# Aerothrust_Module_Stm32_PCB.net
KiCad netlist of a schematic drawn in EAGLE
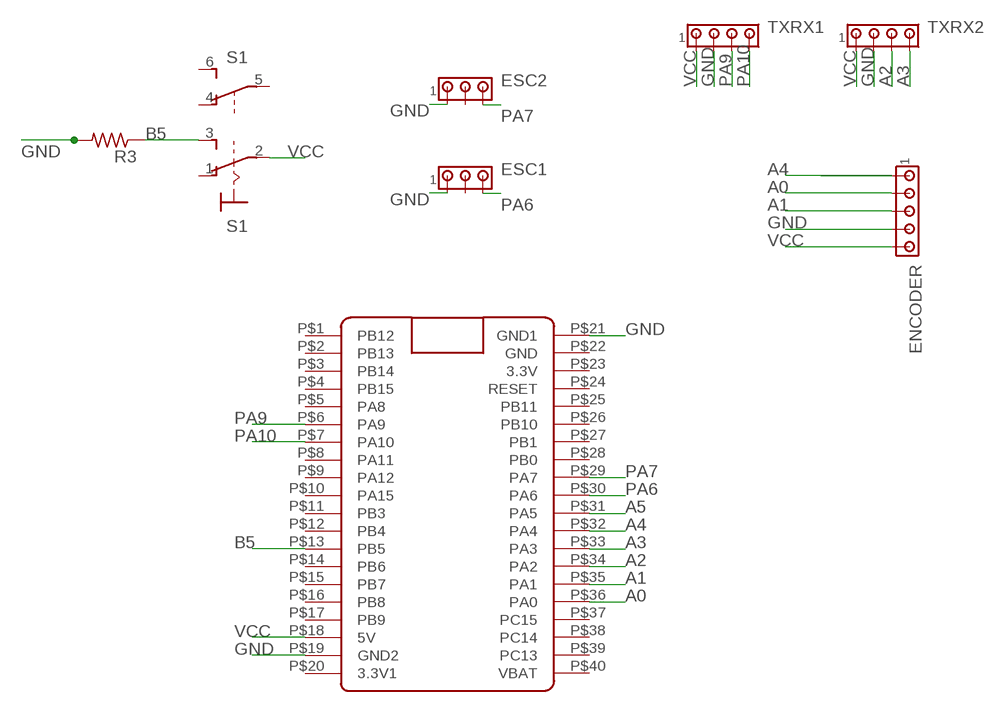
[diagram p0: schematic, sheet 1]

(export (version "E")
  (design (tool "Eeschema 10.0.6"))
  (components
    (comp (ref "ENCODER")
      (value "MTA05-100")
      (footprint "eagle-import:10X05MTA")
      (libsource (lib "eagle-import") (part "MTA05-100"))
    )
    (comp (ref "ESC1")
      (value "MTA03-100")
      (footprint "eagle-import:10X03MTA")
      (libsource (lib "eagle-import") (part "MTA03-100"))
    )
    (comp (ref "ESC2")
      (value "MTA03-100")
      (footprint "eagle-import:10X03MTA")
      (libsource (lib "eagle-import") (part "MTA03-100"))
    )
    (comp (ref "R3")
      (value "R-US_0207/10")
      (footprint "eagle-import:0207_10")
      (libsource (lib "eagle-import") (part "R-US_0207/10"))
    )
    (comp (ref "S1")
      (value "320-938")
      (footprint "eagle-import:320-938")
      (libsource (lib "eagle-import") (part "320-938"))
    )
    (comp (ref "TXRX1")
      (value "MTA04-100")
      (footprint "eagle-import:10X04MTA")
      (libsource (lib "eagle-import") (part "MTA04-100"))
    )
    (comp (ref "TXRX2")
      (value "MTA04-100")
      (footprint "eagle-import:10X04MTA")
      (libsource (lib "eagle-import") (part "MTA04-100"))
    )
    (comp (ref "U$1")
      (value "BLUE_PILL")
      (footprint "eagle-import:BLUE_PILL")
      (libsource (lib "eagle-import") (part "BLUE_PILL"))
    )
  )
  (nets
    (net (code "1") (name "/A0") (class "Default")
      (node (ref "ENCODER") (pin "2") (pinfunction "2_2") (pintype "passive"))
      (node (ref "U$1") (pin "P$36") (pinfunction "PA0_P$36") (pintype "bidirectional"))
    )
    (net (code "2") (name "/A1") (class "Default")
      (node (ref "ENCODER") (pin "3") (pinfunction "3_3") (pintype "passive"))
      (node (ref "U$1") (pin "P$35") (pinfunction "PA1_P$35") (pintype "bidirectional"))
    )
    (net (code "3") (name "/A2") (class "Default")
      (node (ref "TXRX2") (pin "3") (pinfunction "3_3") (pintype "passive"))
      (node (ref "U$1") (pin "P$34") (pinfunction "PA2_P$34") (pintype "bidirectional"))
    )
    (net (code "4") (name "/A3") (class "Default")
      (node (ref "TXRX2") (pin "4") (pinfunction "4_4") (pintype "passive"))
      (node (ref "U$1") (pin "P$33") (pinfunction "PA3_P$33") (pintype "bidirectional"))
    )
    (net (code "5") (name "/A4") (class "Default")
      (node (ref "ENCODER") (pin "1") (pinfunction "1_1") (pintype "passive"))
      (node (ref "U$1") (pin "P$32") (pinfunction "PA4_P$32") (pintype "bidirectional"))
    )
    (net (code "6") (name "/A5") (class "Default")
      (node (ref "U$1") (pin "P$31") (pinfunction "PA5_P$31") (pintype "bidirectional"))
    )
    (net (code "7") (name "/B5") (class "Default")
      (node (ref "R3") (pin "1") (pinfunction "1_1") (pintype "passive"))
      (node (ref "S1") (pin "3") (pinfunction "S_3") (pintype "passive"))
      (node (ref "U$1") (pin "P$13") (pinfunction "PB5_P$13") (pintype "bidirectional"))
    )
    (net (code "8") (name "/GND") (class "Default")
      (node (ref "ENCODER") (pin "4") (pinfunction "4_4") (pintype "passive"))
      (node (ref "ESC1") (pin "1") (pinfunction "1_1") (pintype "passive"))
      (node (ref "ESC2") (pin "1") (pinfunction "1_1") (pintype "passive"))
      (node (ref "R3") (pin "2") (pinfunction "2_2") (pintype "passive"))
      (node (ref "TXRX1") (pin "2") (pinfunction "2_2") (pintype "passive"))
      (node (ref "TXRX2") (pin "2") (pinfunction "2_2") (pintype "passive"))
      (node (ref "U$1") (pin "P$19") (pinfunction "GND2_P$19") (pintype "bidirectional"))
      (node (ref "U$1") (pin "P$21") (pinfunction "GND1_P$21") (pintype "power_in"))
    )
    (net (code "9") (name "/PA6") (class "Default")
      (node (ref "ESC1") (pin "3") (pinfunction "3_3") (pintype "passive"))
      (node (ref "U$1") (pin "P$30") (pinfunction "PA6_P$30") (pintype "bidirectional"))
    )
    (net (code "10") (name "/PA7") (class "Default")
      (node (ref "ESC2") (pin "3") (pinfunction "3_3") (pintype "passive"))
      (node (ref "U$1") (pin "P$29") (pinfunction "PA7_P$29") (pintype "bidirectional"))
    )
    (net (code "11") (name "/PA9") (class "Default")
      (node (ref "TXRX1") (pin "3") (pinfunction "3_3") (pintype "passive"))
      (node (ref "U$1") (pin "P$6") (pinfunction "PA9_P$6") (pintype "bidirectional"))
    )
    (net (code "12") (name "/PA10") (class "Default")
      (node (ref "TXRX1") (pin "4") (pinfunction "4_4") (pintype "passive"))
      (node (ref "U$1") (pin "P$7") (pinfunction "PA10_P$7") (pintype "bidirectional"))
    )
    (net (code "13") (name "/VCC") (class "Default")
      (node (ref "ENCODER") (pin "5") (pinfunction "5_5") (pintype "passive"))
      (node (ref "S1") (pin "2") (pinfunction "P_2") (pintype "passive"))
      (node (ref "TXRX1") (pin "1") (pinfunction "1_1") (pintype "passive"))
      (node (ref "TXRX2") (pin "1") (pinfunction "1_1") (pintype "passive"))
      (node (ref "U$1") (pin "P$18") (pinfunction "5V_P$18") (pintype "bidirectional"))
    )
    (net (code "14") (name "unconnected-(ESC1-Pad2)") (class "Default")
      (node (ref "ESC1") (pin "2") (pinfunction "2_2") (pintype "passive"))
    )
    (net (code "15") (name "unconnected-(ESC2-Pad2)") (class "Default")
      (node (ref "ESC2") (pin "2") (pinfunction "2_2") (pintype "passive"))
    )
    (net (code "16") (name "unconnected-(S1A-O-Pad1)") (class "Default")
      (node (ref "S1") (pin "1") (pinfunction "O_1") (pintype "passive"))
    )
    (net (code "17") (name "unconnected-(S1B-O-Pad4)") (class "Default")
      (node (ref "S1") (pin "4") (pinfunction "O_4") (pintype "passive"))
    )
    (net (code "18") (name "unconnected-(S1B-P-Pad5)") (class "Default")
      (node (ref "S1") (pin "5") (pinfunction "P_5") (pintype "passive"))
    )
    (net (code "19") (name "unconnected-(S1B-S-Pad6)") (class "Default")
      (node (ref "S1") (pin "6") (pinfunction "S_6") (pintype "passive"))
    )
    (net (code "20") (name "unconnected-(U$1-3.3V-PadP$23)") (class "Default")
      (node (ref "U$1") (pin "P$23") (pinfunction "3.3V_P$23") (pintype "bidirectional"))
    )
    (net (code "21") (name "unconnected-(U$1-3.3V1-PadP$20)") (class "Default")
      (node (ref "U$1") (pin "P$20") (pinfunction "3.3V1_P$20") (pintype "bidirectional"))
    )
    (net (code "22") (name "unconnected-(U$1-GND-PadP$22)") (class "Default")
      (node (ref "U$1") (pin "P$22") (pinfunction "GND_P$22") (pintype "bidirectional"))
    )
    (net (code "23") (name "unconnected-(U$1-PA8-PadP$5)") (class "Default")
      (node (ref "U$1") (pin "P$5") (pinfunction "PA8_P$5") (pintype "bidirectional"))
    )
    (net (code "24") (name "unconnected-(U$1-PA11-PadP$8)") (class "Default")
      (node (ref "U$1") (pin "P$8") (pinfunction "PA11_P$8") (pintype "bidirectional"))
    )
    (net (code "25") (name "unconnected-(U$1-PA12-PadP$9)") (class "Default")
      (node (ref "U$1") (pin "P$9") (pinfunction "PA12_P$9") (pintype "bidirectional"))
    )
    (net (code "26") (name "unconnected-(U$1-PA15-PadP$10)") (class "Default")
      (node (ref "U$1") (pin "P$10") (pinfunction "PA15_P$10") (pintype "bidirectional"))
    )
    (net (code "27") (name "unconnected-(U$1-PB0-PadP$28)") (class "Default")
      (node (ref "U$1") (pin "P$28") (pinfunction "PB0_P$28") (pintype "bidirectional"))
    )
    (net (code "28") (name "unconnected-(U$1-PB1-PadP$27)") (class "Default")
      (node (ref "U$1") (pin "P$27") (pinfunction "PB1_P$27") (pintype "bidirectional"))
    )
    (net (code "29") (name "unconnected-(U$1-PB3-PadP$11)") (class "Default")
      (node (ref "U$1") (pin "P$11") (pinfunction "PB3_P$11") (pintype "bidirectional"))
    )
    (net (code "30") (name "unconnected-(U$1-PB4-PadP$12)") (class "Default")
      (node (ref "U$1") (pin "P$12") (pinfunction "PB4_P$12") (pintype "bidirectional"))
    )
    (net (code "31") (name "unconnected-(U$1-PB6-PadP$14)") (class "Default")
      (node (ref "U$1") (pin "P$14") (pinfunction "PB6_P$14") (pintype "bidirectional"))
    )
    (net (code "32") (name "unconnected-(U$1-PB7-PadP$15)") (class "Default")
      (node (ref "U$1") (pin "P$15") (pinfunction "PB7_P$15") (pintype "bidirectional"))
    )
    (net (code "33") (name "unconnected-(U$1-PB8-PadP$16)") (class "Default")
      (node (ref "U$1") (pin "P$16") (pinfunction "PB8_P$16") (pintype "bidirectional"))
    )
    (net (code "34") (name "unconnected-(U$1-PB9-PadP$17)") (class "Default")
      (node (ref "U$1") (pin "P$17") (pinfunction "PB9_P$17") (pintype "bidirectional"))
    )
    (net (code "35") (name "unconnected-(U$1-PB10-PadP$26)") (class "Default")
      (node (ref "U$1") (pin "P$26") (pinfunction "PB10_P$26") (pintype "bidirectional"))
    )
    (net (code "36") (name "unconnected-(U$1-PB11-PadP$25)") (class "Default")
      (node (ref "U$1") (pin "P$25") (pinfunction "PB11_P$25") (pintype "bidirectional"))
    )
    (net (code "37") (name "unconnected-(U$1-PB12-PadP$1)") (class "Default")
      (node (ref "U$1") (pin "P$1") (pinfunction "PB12_P$1") (pintype "bidirectional"))
    )
    (net (code "38") (name "unconnected-(U$1-PB13-PadP$2)") (class "Default")
      (node (ref "U$1") (pin "P$2") (pinfunction "PB13_P$2") (pintype "bidirectional"))
    )
    (net (code "39") (name "unconnected-(U$1-PB14-PadP$3)") (class "Default")
      (node (ref "U$1") (pin "P$3") (pinfunction "PB14_P$3") (pintype "bidirectional"))
    )
    (net (code "40") (name "unconnected-(U$1-PB15-PadP$4)") (class "Default")
      (node (ref "U$1") (pin "P$4") (pinfunction "PB15_P$4") (pintype "bidirectional"))
    )
    (net (code "41") (name "unconnected-(U$1-PC13-PadP$39)") (class "Default")
      (node (ref "U$1") (pin "P$39") (pinfunction "PC13_P$39") (pintype "bidirectional"))
    )
    (net (code "42") (name "unconnected-(U$1-PC14-PadP$38)") (class "Default")
      (node (ref "U$1") (pin "P$38") (pinfunction "PC14_P$38") (pintype "bidirectional"))
    )
    (net (code "43") (name "unconnected-(U$1-PC15-PadP$37)") (class "Default")
      (node (ref "U$1") (pin "P$37") (pinfunction "PC15_P$37") (pintype "bidirectional"))
    )
    (net (code "44") (name "unconnected-(U$1-RESET-PadP$24)") (class "Default")
      (node (ref "U$1") (pin "P$24") (pinfunction "RESET_P$24") (pintype "bidirectional"))
    )
    (net (code "45") (name "unconnected-(U$1-VBAT-PadP$40)") (class "Default")
      (node (ref "U$1") (pin "P$40") (pinfunction "VBAT_P$40") (pintype "bidirectional"))
    )
  )
)
